# ShieldThunder.net
KiCad netlist of a schematic drawn in EAGLE
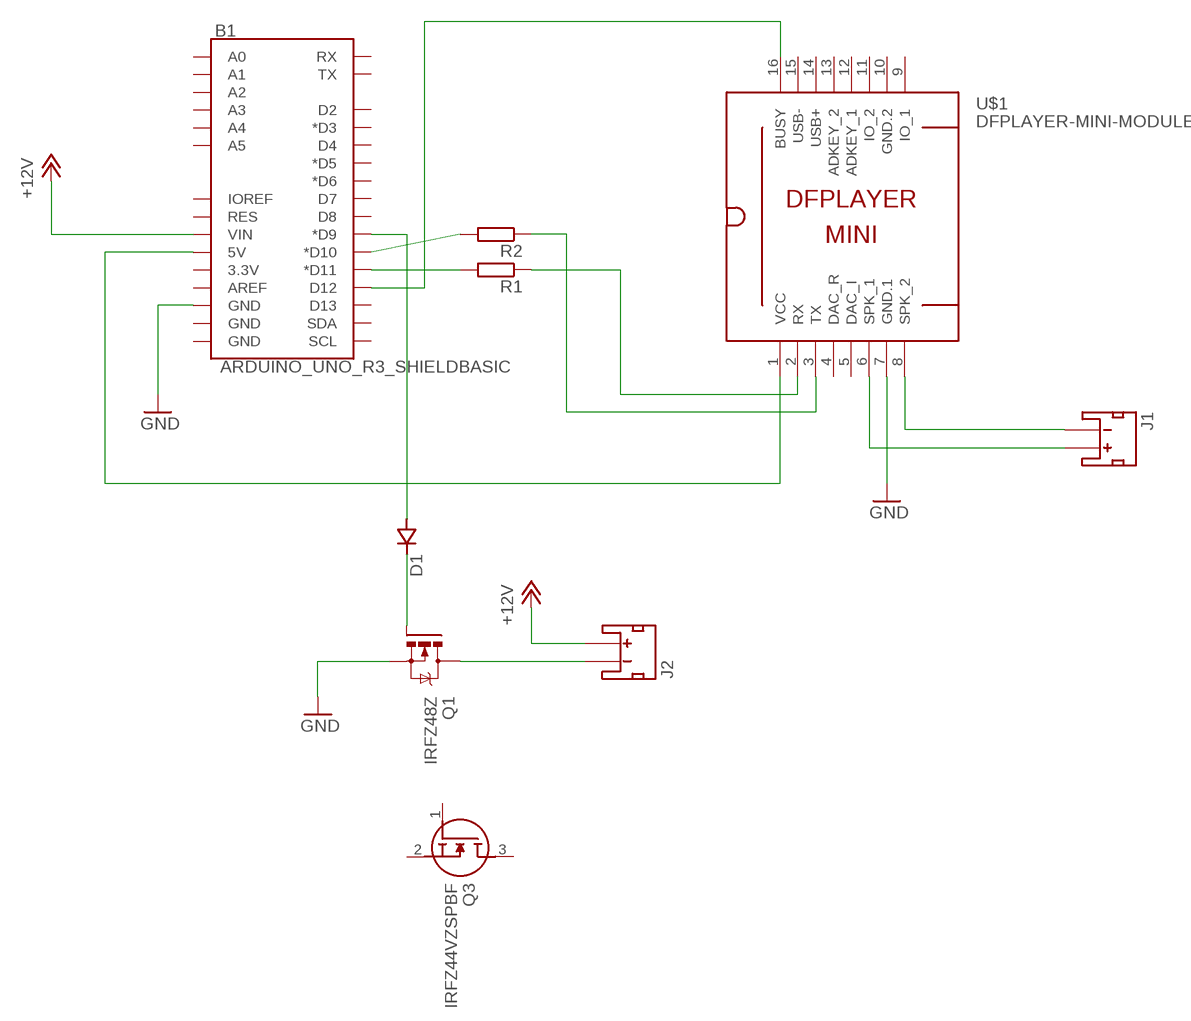
[diagram p0: schematic, sheet 1]

(export (version "E")
  (design (tool "Eeschema 10.0.6"))
  (components
    (comp (ref "B1")
      (value "ARDUINO_UNO_R3_SHIELDBASIC")
      (footprint "eagle-import:UNO_R3_SHIELD")
      (libsource (lib "eagle-import") (part "ARDUINO_UNO_R3_SHIELDBASIC"))
    )
    (comp (ref "D1")
      (value "DSOT23")
      (footprint "eagle-import:SOT-23")
      (fields (field (name "MPN") "CDSOT23-T03"))
      (libsource (lib "eagle-import") (part "DSOT23"))
    )
    (comp (ref "J1")
      (value "JST_2MM_MALE")
      (footprint "eagle-import:JST-2-SMD")
      (libsource (lib "eagle-import") (part "JST_2MM_MALE"))
    )
    (comp (ref "J2")
      (value "JST_2MM_MALE")
      (footprint "eagle-import:JST-2-SMD")
      (libsource (lib "eagle-import") (part "JST_2MM_MALE"))
    )
    (comp (ref "Q1")
      (value "IRFZ48Z")
      (footprint "eagle-import:TO220BH")
      (libsource (lib "eagle-import") (part "IRFZ48Z"))
    )
    (comp (ref "Q3")
      (value "IRFZ44VZSPBF")
      (footprint "eagle-import:D2PAK(TO-263AB)")
      (fields (field (name "MOUSER_PART_NUMBER") "942-IRFZ44VZSPBF"))
      (libsource (lib "eagle-import") (part "IRFZ44VZSPBF"))
    )
    (comp (ref "R1")
      (value "R-EU_R0805")
      (footprint "eagle-import:R0805")
      (fields (field (name "SPICEPREFIX") "1K"))
      (libsource (lib "eagle-import") (part "R-EU_R0805"))
    )
    (comp (ref "R2")
      (value "R-EU_R0805")
      (footprint "eagle-import:R0805")
      (fields (field (name "SPICEPREFIX") "1K"))
      (libsource (lib "eagle-import") (part "R-EU_R0805"))
    )
    (comp (ref "U$1")
      (value "DFPLAYER-MINI-MODULE")
      (footprint "eagle-import:DFPLAYER-MINI-MODULE")
      (libsource (lib "eagle-import") (part "DFPLAYER-MINI-MODULE"))
    )
  )
  (nets
    (net (code "1") (name "+12V") (class "Default")
      (node (ref "B1") (pin "VIN") (pinfunction "VIN_VIN") (pintype "bidirectional"))
      (node (ref "J2") (pin "2") (pinfunction "+_2") (pintype "bidirectional"))
    )
    (net (code "2") (name "/GND.2") (class "Default")
      (node (ref "U$1") (pin "10") (pinfunction "GND.2_10") (pintype "power_in"))
    )
    (net (code "3") (name "GND") (class "Default")
      (node (ref "B1") (pin "GND@2") (pinfunction "GND_GND@2") (pintype "bidirectional"))
      (node (ref "Q1") (pin "S") (pinfunction "S_S") (pintype "passive"))
      (node (ref "U$1") (pin "7") (pinfunction "GND.1_7") (pintype "power_in"))
    )
    (net (code "4") (name "Net-(B1-*D9)") (class "Default")
      (node (ref "B1") (pin "D9") (pinfunction "*D9_D9") (pintype "bidirectional"))
      (node (ref "D1") (pin "3") (pinfunction "A_3") (pintype "passive"))
    )
    (net (code "5") (name "Net-(B1-*D10)") (class "Default")
      (node (ref "B1") (pin "D10") (pinfunction "*D10_D10") (pintype "bidirectional"))
      (node (ref "R2") (pin "2") (pinfunction "2_2") (pintype "passive"))
    )
    (net (code "6") (name "Net-(B1-*D11)") (class "Default")
      (node (ref "B1") (pin "D11") (pinfunction "*D11_D11") (pintype "bidirectional"))
      (node (ref "R1") (pin "2") (pinfunction "2_2") (pintype "passive"))
    )
    (net (code "7") (name "Net-(D1-C)") (class "Default")
      (node (ref "D1") (pin "1") (pinfunction "C_1") (pintype "passive"))
      (node (ref "Q1") (pin "G") (pinfunction "G_G") (pintype "passive"))
    )
    (net (code "8") (name "Net-(J1-+)") (class "Default")
      (node (ref "J1") (pin "2") (pinfunction "+_2") (pintype "bidirectional"))
      (node (ref "U$1") (pin "6") (pinfunction "SPK_1_6") (pintype "bidirectional"))
    )
    (net (code "9") (name "Net-(J1--)") (class "Default")
      (node (ref "J1") (pin "1") (pinfunction "-_1") (pintype "bidirectional"))
      (node (ref "U$1") (pin "8") (pinfunction "SPK_2_8") (pintype "bidirectional"))
    )
    (net (code "10") (name "Net-(J2--)") (class "Default")
      (node (ref "J2") (pin "1") (pinfunction "-_1") (pintype "bidirectional"))
      (node (ref "Q1") (pin "D") (pinfunction "D_D") (pintype "passive"))
    )
    (net (code "11") (name "Net-(U$1-BUSY)") (class "Default")
      (node (ref "B1") (pin "D12") (pinfunction "D12_D12") (pintype "bidirectional"))
      (node (ref "U$1") (pin "16") (pinfunction "BUSY_16") (pintype "bidirectional"))
    )
    (net (code "12") (name "Net-(U$1-RX)") (class "Default")
      (node (ref "R1") (pin "1") (pinfunction "1_1") (pintype "passive"))
      (node (ref "U$1") (pin "2") (pinfunction "RX_2") (pintype "bidirectional"))
    )
    (net (code "13") (name "Net-(U$1-TX)") (class "Default")
      (node (ref "R2") (pin "1") (pinfunction "1_1") (pintype "passive"))
      (node (ref "U$1") (pin "3") (pinfunction "TX_3") (pintype "bidirectional"))
    )
    (net (code "14") (name "Net-(U$1-VCC)") (class "Default")
      (node (ref "B1") (pin "5V") (pinfunction "5V_5V") (pintype "bidirectional"))
      (node (ref "U$1") (pin "1") (pinfunction "VCC_1") (pintype "power_in"))
    )
    (net (code "15") (name "unconnected-(B1-*D3-PadD3)") (class "Default")
      (node (ref "B1") (pin "D3") (pinfunction "*D3_D3") (pintype "bidirectional"))
    )
    (net (code "16") (name "unconnected-(B1-*D5-PadD5)") (class "Default")
      (node (ref "B1") (pin "D5") (pinfunction "*D5_D5") (pintype "bidirectional"))
    )
    (net (code "17") (name "unconnected-(B1-*D6-PadD6)") (class "Default")
      (node (ref "B1") (pin "D6") (pinfunction "*D6_D6") (pintype "bidirectional"))
    )
    (net (code "18") (name "unconnected-(B1-GND-PadGND@0)") (class "Default")
      (node (ref "B1") (pin "GND@0") (pinfunction "GND_GND@0") (pintype "bidirectional"))
    )
    (net (code "19") (name "unconnected-(B1-GND-PadGND@1)") (class "Default")
      (node (ref "B1") (pin "GND@1") (pinfunction "GND_GND@1") (pintype "bidirectional"))
    )
    (net (code "20") (name "unconnected-(B1-Pad3.3V)") (class "Default")
      (node (ref "B1") (pin "3.3V") (pinfunction "3.3V_3.3V") (pintype "bidirectional"))
    )
    (net (code "21") (name "unconnected-(B1-PadA0)") (class "Default")
      (node (ref "B1") (pin "A0") (pinfunction "A0_A0") (pintype "bidirectional"))
    )
    (net (code "22") (name "unconnected-(B1-PadA1)") (class "Default")
      (node (ref "B1") (pin "A1") (pinfunction "A1_A1") (pintype "bidirectional"))
    )
    (net (code "23") (name "unconnected-(B1-PadA2)") (class "Default")
      (node (ref "B1") (pin "A2") (pinfunction "A2_A2") (pintype "bidirectional"))
    )
    (net (code "24") (name "unconnected-(B1-PadA3)") (class "Default")
      (node (ref "B1") (pin "A3") (pinfunction "A3_A3") (pintype "bidirectional"))
    )
    (net (code "25") (name "unconnected-(B1-PadA4)") (class "Default")
      (node (ref "B1") (pin "A4") (pinfunction "A4_A4") (pintype "bidirectional"))
    )
    (net (code "26") (name "unconnected-(B1-PadA5)") (class "Default")
      (node (ref "B1") (pin "A5") (pinfunction "A5_A5") (pintype "bidirectional"))
    )
    (net (code "27") (name "unconnected-(B1-PadAREF)") (class "Default")
      (node (ref "B1") (pin "AREF") (pinfunction "AREF_AREF") (pintype "bidirectional"))
    )
    (net (code "28") (name "unconnected-(B1-PadD2)") (class "Default")
      (node (ref "B1") (pin "D2") (pinfunction "D2_D2") (pintype "bidirectional"))
    )
    (net (code "29") (name "unconnected-(B1-PadD4)") (class "Default")
      (node (ref "B1") (pin "D4") (pinfunction "D4_D4") (pintype "bidirectional"))
    )
    (net (code "30") (name "unconnected-(B1-PadD7)") (class "Default")
      (node (ref "B1") (pin "D7") (pinfunction "D7_D7") (pintype "bidirectional"))
    )
    (net (code "31") (name "unconnected-(B1-PadD8)") (class "Default")
      (node (ref "B1") (pin "D8") (pinfunction "D8_D8") (pintype "bidirectional"))
    )
    (net (code "32") (name "unconnected-(B1-PadD13)") (class "Default")
      (node (ref "B1") (pin "D13") (pinfunction "D13_D13") (pintype "bidirectional"))
    )
    (net (code "33") (name "unconnected-(B1-PadIOREF)") (class "Default")
      (node (ref "B1") (pin "IOREF") (pinfunction "IOREF_IOREF") (pintype "bidirectional"))
    )
    (net (code "34") (name "unconnected-(B1-PadRES)") (class "Default")
      (node (ref "B1") (pin "RES") (pinfunction "RES_RES") (pintype "bidirectional"))
    )
    (net (code "35") (name "unconnected-(B1-PadRX)") (class "Default")
      (node (ref "B1") (pin "RX") (pinfunction "RX_RX") (pintype "bidirectional"))
    )
    (net (code "36") (name "unconnected-(B1-PadSCL)") (class "Default")
      (node (ref "B1") (pin "SCL") (pinfunction "SCL_SCL") (pintype "bidirectional"))
    )
    (net (code "37") (name "unconnected-(B1-PadSDA)") (class "Default")
      (node (ref "B1") (pin "SDA") (pinfunction "SDA_SDA") (pintype "bidirectional"))
    )
    (net (code "38") (name "unconnected-(B1-PadTX)") (class "Default")
      (node (ref "B1") (pin "TX") (pinfunction "TX_TX") (pintype "bidirectional"))
    )
    (net (code "39") (name "unconnected-(J1-PAD1-PadNC1)") (class "Default")
      (node (ref "J1") (pin "NC1") (pinfunction "PAD1_NC1") (pintype "bidirectional"))
    )
    (net (code "40") (name "unconnected-(J1-PAD2-PadNC2)") (class "Default")
      (node (ref "J1") (pin "NC2") (pinfunction "PAD2_NC2") (pintype "bidirectional"))
    )
    (net (code "41") (name "unconnected-(J2-PAD1-PadNC1)") (class "Default")
      (node (ref "J2") (pin "NC1") (pinfunction "PAD1_NC1") (pintype "bidirectional"))
    )
    (net (code "42") (name "unconnected-(J2-PAD2-PadNC2)") (class "Default")
      (node (ref "J2") (pin "NC2") (pinfunction "PAD2_NC2") (pintype "bidirectional"))
    )
    (net (code "43") (name "unconnected-(Q3-D-Pad3)") (class "Default")
      (node (ref "Q3") (pin "3") (pinfunction "D_3") (pintype "bidirectional"))
    )
    (net (code "44") (name "unconnected-(Q3-G-Pad1)") (class "Default")
      (node (ref "Q3") (pin "1") (pinfunction "G_1") (pintype "bidirectional"))
    )
    (net (code "45") (name "unconnected-(Q3-S-Pad2)") (class "Default")
      (node (ref "Q3") (pin "2") (pinfunction "S_2") (pintype "bidirectional"))
    )
    (net (code "46") (name "unconnected-(U$1-ADKEY_1-Pad12)") (class "Default")
      (node (ref "U$1") (pin "12") (pinfunction "ADKEY_1_12") (pintype "bidirectional"))
    )
    (net (code "47") (name "unconnected-(U$1-ADKEY_2-Pad13)") (class "Default")
      (node (ref "U$1") (pin "13") (pinfunction "ADKEY_2_13") (pintype "bidirectional"))
    )
    (net (code "48") (name "unconnected-(U$1-DAC_I-Pad5)") (class "Default")
      (node (ref "U$1") (pin "5") (pinfunction "DAC_I_5") (pintype "bidirectional"))
    )
    (net (code "49") (name "unconnected-(U$1-DAC_R-Pad4)") (class "Default")
      (node (ref "U$1") (pin "4") (pinfunction "DAC_R_4") (pintype "bidirectional"))
    )
    (net (code "50") (name "unconnected-(U$1-IO_1-Pad9)") (class "Default")
      (node (ref "U$1") (pin "9") (pinfunction "IO_1_9") (pintype "bidirectional"))
    )
    (net (code "51") (name "unconnected-(U$1-IO_2-Pad11)") (class "Default")
      (node (ref "U$1") (pin "11") (pinfunction "IO_2_11") (pintype "bidirectional"))
    )
    (net (code "52") (name "unconnected-(U$1-USB+-Pad14)") (class "Default")
      (node (ref "U$1") (pin "14") (pinfunction "USB+_14") (pintype "bidirectional"))
    )
    (net (code "53") (name "unconnected-(U$1-USB--Pad15)") (class "Default")
      (node (ref "U$1") (pin "15") (pinfunction "USB-_15") (pintype "bidirectional"))
    )
  )
)
